# PMM.net
KiCad netlist of a schematic drawn in EAGLE
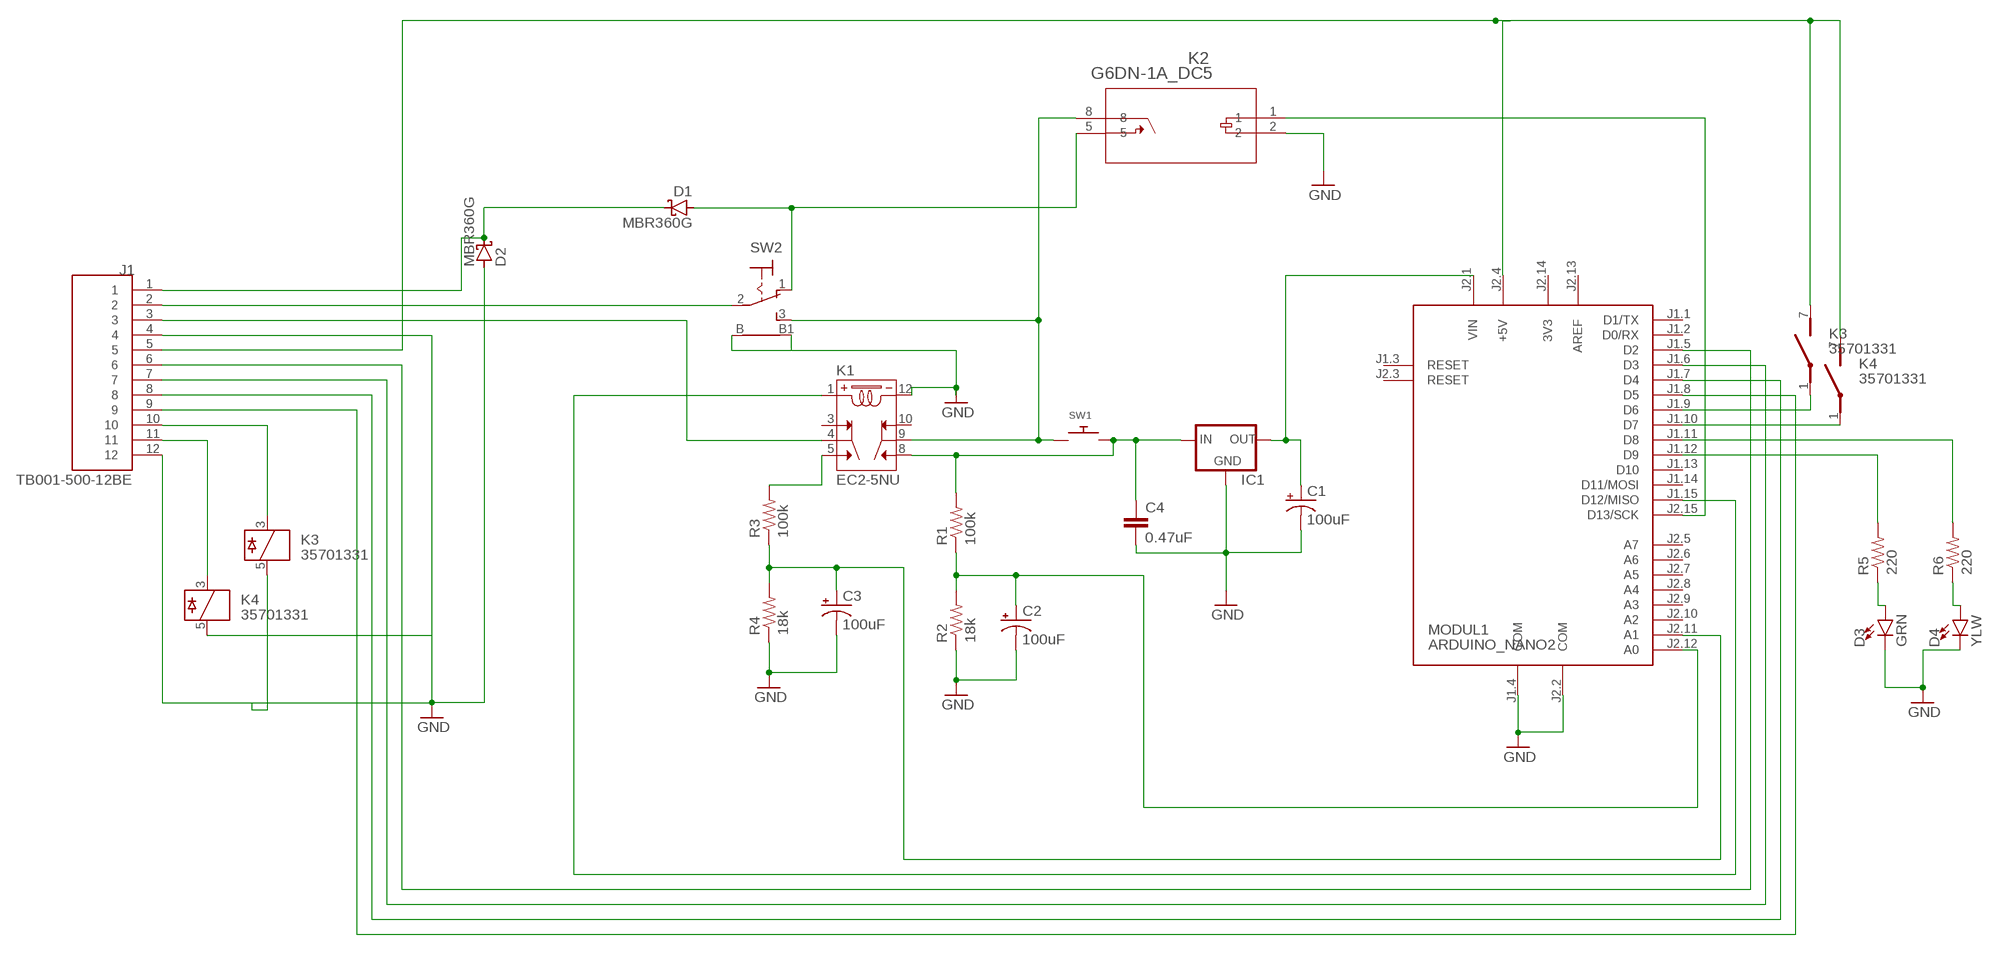
[diagram p0: schematic, sheet 1]

(export (version "E")
  (design (tool "Eeschema 10.0.6"))
  (components
    (comp (ref "C1")
      (value "100uF")
      (footprint "eagle-import:E2,5-7")
      (libsource (lib "eagle-import") (part "CPOL-USE2.5-7"))
    )
    (comp (ref "C2")
      (value "100uF")
      (footprint "eagle-import:E2,5-7")
      (libsource (lib "eagle-import") (part "CPOL-USE2.5-7"))
    )
    (comp (ref "C3")
      (value "100uF")
      (footprint "eagle-import:E2,5-7")
      (libsource (lib "eagle-import") (part "CPOL-USE2.5-7"))
    )
    (comp (ref "C4")
      (value "0.47uF")
      (footprint "eagle-import:C10B6")
      (libsource (lib "eagle-import") (part "C10/6"))
    )
    (comp (ref "D1")
      (value "MBR360G")
      (footprint "eagle-import:DO201AD")
      (fields
        (field (name "DIGIKEY_PART_NUMBER") "MBR360GOS-ND")
        (field (name "MANUFACTURER") "ON Semiconductor")
        (field (name "CREATED_BY") "PCBLayout.com")
      )
      (libsource (lib "eagle-import") (part "MBR360G"))
    )
    (comp (ref "D2")
      (value "MBR360G")
      (footprint "eagle-import:DO201AD")
      (fields
        (field (name "DIGIKEY_PART_NUMBER") "MBR360GOS-ND")
        (field (name "MANUFACTURER") "ON Semiconductor")
        (field (name "CREATED_BY") "PCBLayout.com")
      )
      (libsource (lib "eagle-import") (part "MBR360G"))
    )
    (comp (ref "D3")
      (value "GRN")
      (footprint "eagle-import:LED_5MM-KIT")
      (libsource (lib "eagle-import") (part "LED5MM-KIT"))
    )
    (comp (ref "D4")
      (value "YLW")
      (footprint "eagle-import:LED_5MM-KIT")
      (libsource (lib "eagle-import") (part "LED5MM-KIT"))
    )
    (comp (ref "IC1")
      (value "78XXS")
      (footprint "eagle-import:78XXS")
      (libsource (lib "eagle-import") (part "78XXS"))
    )
    (comp (ref "J1")
      (value "TB001-500-12BE")
      (footprint "eagle-import:CUI_TB001-500-12BE")
      (fields (field (name "MANUFACTURER") "CUI"))
      (libsource (lib "eagle-import") (part "TB001-500-12BE"))
    )
    (comp (ref "K1")
      (value "EC2-5NU")
      (footprint "eagle-import:RELAY_EC2-5NU")
      (fields (field (name "DIGI-KEY_PART_NUMBER") "399-11052-5-ND") (field (name "MF") "KEMET"))
      (libsource (lib "eagle-import") (part "EC2-5NU"))
    )
    (comp (ref "K2")
      (value "G6DN-1A_DC5")
      (footprint "eagle-import:RELAY_G6DN-1A_OMR")
      (fields
        (field (name "MANUFACTURER_PART_NUMBER") "G6DN-1A DC5")
        (field (name "COPYRIGHT") "Copyright (C) 2018 Accelerated Designs. All rights reserved")
      )
      (libsource (lib "eagle-import") (part "G6DN-1A_DC5"))
    )
    (comp (ref "K3")
      (value "35701331")
      (footprint "eagle-import:REED")
      (libsource (lib "eagle-import") (part "35701331"))
    )
    (comp (ref "K4")
      (value "35701331")
      (footprint "eagle-import:REED")
      (libsource (lib "eagle-import") (part "35701331"))
    )
    (comp (ref "MODUL1")
      (value "ARDUINO_NANO2")
      (footprint "eagle-import:ARDUINO_NANO2")
      (libsource (lib "eagle-import") (part "ARDUINO_NANO2"))
    )
    (comp (ref "R1")
      (value "100k")
      (footprint "eagle-import:0207_12")
      (libsource (lib "eagle-import") (part "R-US_0207/12"))
    )
    (comp (ref "R2")
      (value "18k")
      (footprint "eagle-import:0207_12")
      (libsource (lib "eagle-import") (part "R-US_0207/12"))
    )
    (comp (ref "R3")
      (value "100k")
      (footprint "eagle-import:0207_12")
      (libsource (lib "eagle-import") (part "R-US_0207/12"))
    )
    (comp (ref "R4")
      (value "18k")
      (footprint "eagle-import:0207_12")
      (libsource (lib "eagle-import") (part "R-US_0207/12"))
    )
    (comp (ref "R5")
      (value "220")
      (footprint "eagle-import:0207_12")
      (libsource (lib "eagle-import") (part "R-US_0207/12"))
    )
    (comp (ref "R6")
      (value "220")
      (footprint "eagle-import:0207_12")
      (libsource (lib "eagle-import") (part "R-US_0207/12"))
    )
    (comp (ref "SW1")
      (value "SWITCH_PUSHBUTTONON-MOM.2")
      (footprint "eagle-import:TACT_PANA-EVQ")
      (libsource (lib "eagle-import") (part "SWITCH_PUSHBUTTONON-MOM.2"))
    )
    (comp (ref "SW2")
      (value "M20130M2013S2A2W30")
      (footprint "eagle-import:M201_30")
      (libsource (lib "eagle-import") (part "M20130M2013S2A2W30"))
    )
  )
  (nets
    (net (code "1") (name "/3V3") (class "Default")
      (node (ref "MODUL1") (pin "J2.14") (pinfunction "3V3_J2.14") (pintype "power_in"))
    )
    (net (code "2") (name "/AREF") (class "Default")
      (node (ref "MODUL1") (pin "J2.13") (pinfunction "AREF_J2.13") (pintype "power_in"))
    )
    (net (code "3") (name "GND") (class "Default")
      (node (ref "C1") (pin "-") (pinfunction "-_-") (pintype "passive"))
      (node (ref "C2") (pin "-") (pinfunction "-_-") (pintype "passive"))
      (node (ref "C3") (pin "-") (pinfunction "-_-") (pintype "passive"))
      (node (ref "C4") (pin "2") (pinfunction "2_2") (pintype "passive"))
      (node (ref "D2") (pin "A") (pinfunction "A_A") (pintype "passive"))
      (node (ref "D3") (pin "K") (pinfunction "C_K") (pintype "passive"))
      (node (ref "D4") (pin "K") (pinfunction "C_K") (pintype "passive"))
      (node (ref "IC1") (pin "GND") (pinfunction "GND_GND") (pintype "input"))
      (node (ref "J1") (pin "12") (pinfunction "12_12") (pintype "passive"))
      (node (ref "J1") (pin "4") (pinfunction "4_4") (pintype "passive"))
      (node (ref "K1") (pin "12") (pinfunction "12_12") (pintype "passive"))
      (node (ref "K2") (pin "2") (pinfunction "2_2") (pintype "passive"))
      (node (ref "K3") (pin "5") (pinfunction "5_5") (pintype "passive"))
      (node (ref "K4") (pin "5") (pinfunction "5_5") (pintype "passive"))
      (node (ref "MODUL1") (pin "J1.4") (pinfunction "COM_J1.4") (pintype "power_in"))
      (node (ref "MODUL1") (pin "J2.2") (pinfunction "COM_J2.2") (pintype "power_in"))
      (node (ref "R2") (pin "1") (pinfunction "1_1") (pintype "passive"))
      (node (ref "R4") (pin "1") (pinfunction "1_1") (pintype "passive"))
      (node (ref "SW2") (pin "B") (pinfunction "B_B") (pintype "passive"))
      (node (ref "SW2") (pin "B1") (pinfunction "B1_B1") (pintype "passive"))
    )
    (net (code "4") (name "Net-(C4-Pad1)") (class "Default")
      (node (ref "C4") (pin "1") (pinfunction "1_1") (pintype "passive"))
      (node (ref "IC1") (pin "IN") (pinfunction "IN_IN") (pintype "input"))
      (node (ref "K1") (pin "8") (pinfunction "8_8") (pintype "passive"))
      (node (ref "R1") (pin "2") (pinfunction "2_2") (pintype "passive"))
      (node (ref "SW1") (pin "P$2") (pinfunction "P$2_P$2") (pintype "passive"))
    )
    (net (code "5") (name "Net-(D1-PadC)") (class "Default")
      (node (ref "D1") (pin "C") (pinfunction "C_C") (pintype "passive"))
      (node (ref "D2") (pin "C") (pinfunction "C_C") (pintype "passive"))
      (node (ref "J1") (pin "1") (pinfunction "1_1") (pintype "passive"))
    )
    (net (code "6") (name "Net-(D3-PadA)") (class "Default")
      (node (ref "D3") (pin "A") (pinfunction "A_A") (pintype "passive"))
      (node (ref "R5") (pin "1") (pinfunction "1_1") (pintype "passive"))
    )
    (net (code "7") (name "Net-(D4-PadA)") (class "Default")
      (node (ref "D4") (pin "A") (pinfunction "A_A") (pintype "passive"))
      (node (ref "R6") (pin "1") (pinfunction "1_1") (pintype "passive"))
    )
    (net (code "8") (name "Net-(J1-Pad3)") (class "Default")
      (node (ref "J1") (pin "3") (pinfunction "3_3") (pintype "passive"))
      (node (ref "K1") (pin "4") (pinfunction "4_4") (pintype "passive"))
    )
    (net (code "9") (name "Net-(J1-Pad10)") (class "Default")
      (node (ref "J1") (pin "10") (pinfunction "10_10") (pintype "passive"))
      (node (ref "K3") (pin "3") (pinfunction "3_3") (pintype "passive"))
    )
    (net (code "10") (name "Net-(J1-Pad11)") (class "Default")
      (node (ref "J1") (pin "11") (pinfunction "11_11") (pintype "passive"))
      (node (ref "K4") (pin "3") (pinfunction "3_3") (pintype "passive"))
    )
    (net (code "11") (name "Net-(K1-Pad5)") (class "Default")
      (node (ref "K1") (pin "5") (pinfunction "5_5") (pintype "passive"))
      (node (ref "R3") (pin "2") (pinfunction "2_2") (pintype "passive"))
    )
    (net (code "12") (name "Net-(K3B-P)") (class "Default")
      (node (ref "K3") (pin "1") (pinfunction "P_1") (pintype "passive"))
      (node (ref "MODUL1") (pin "J1.9") (pinfunction "D6_J1.9") (pintype "bidirectional"))
    )
    (net (code "13") (name "Net-(K3B-S)") (class "Default")
      (node (ref "J1") (pin "5") (pinfunction "5_5") (pintype "passive"))
      (node (ref "K3") (pin "7") (pinfunction "S_7") (pintype "passive"))
      (node (ref "K4") (pin "7") (pinfunction "S_7") (pintype "passive"))
      (node (ref "MODUL1") (pin "J2.4") (pinfunction "+5V_J2.4") (pintype "power_in"))
    )
    (net (code "14") (name "Net-(K4B-P)") (class "Default")
      (node (ref "K4") (pin "1") (pinfunction "P_1") (pintype "passive"))
      (node (ref "MODUL1") (pin "J1.10") (pinfunction "D7_J1.10") (pintype "bidirectional"))
    )
    (net (code "15") (name "Net-(MODUL1-A0)") (class "Default")
      (node (ref "C2") (pin "+") (pinfunction "+_+") (pintype "passive"))
      (node (ref "MODUL1") (pin "J2.12") (pinfunction "A0_J2.12") (pintype "bidirectional"))
      (node (ref "R1") (pin "1") (pinfunction "1_1") (pintype "passive"))
      (node (ref "R2") (pin "2") (pinfunction "2_2") (pintype "passive"))
    )
    (net (code "16") (name "Net-(MODUL1-A1)") (class "Default")
      (node (ref "C3") (pin "+") (pinfunction "+_+") (pintype "passive"))
      (node (ref "MODUL1") (pin "J2.11") (pinfunction "A1_J2.11") (pintype "bidirectional"))
      (node (ref "R3") (pin "1") (pinfunction "1_1") (pintype "passive"))
      (node (ref "R4") (pin "2") (pinfunction "2_2") (pintype "passive"))
    )
    (net (code "17") (name "Net-(MODUL1-D2)") (class "Default")
      (node (ref "J1") (pin "6") (pinfunction "6_6") (pintype "passive"))
      (node (ref "MODUL1") (pin "J1.5") (pinfunction "D2_J1.5") (pintype "bidirectional"))
    )
    (net (code "18") (name "Net-(MODUL1-D3)") (class "Default")
      (node (ref "J1") (pin "7") (pinfunction "7_7") (pintype "passive"))
      (node (ref "MODUL1") (pin "J1.6") (pinfunction "D3_J1.6") (pintype "bidirectional"))
    )
    (net (code "19") (name "Net-(MODUL1-D4)") (class "Default")
      (node (ref "J1") (pin "8") (pinfunction "8_8") (pintype "passive"))
      (node (ref "MODUL1") (pin "J1.7") (pinfunction "D4_J1.7") (pintype "bidirectional"))
    )
    (net (code "20") (name "Net-(MODUL1-D5)") (class "Default")
      (node (ref "J1") (pin "9") (pinfunction "9_9") (pintype "passive"))
      (node (ref "MODUL1") (pin "J1.8") (pinfunction "D5_J1.8") (pintype "bidirectional"))
    )
    (net (code "21") (name "Net-(MODUL1-D8)") (class "Default")
      (node (ref "MODUL1") (pin "J1.11") (pinfunction "D8_J1.11") (pintype "bidirectional"))
      (node (ref "R6") (pin "2") (pinfunction "2_2") (pintype "passive"))
    )
    (net (code "22") (name "Net-(MODUL1-D9)") (class "Default")
      (node (ref "MODUL1") (pin "J1.12") (pinfunction "D9_J1.12") (pintype "bidirectional"))
      (node (ref "R5") (pin "2") (pinfunction "2_2") (pintype "passive"))
    )
    (net (code "23") (name "Net-(MODUL1-D12{slash}MISO)") (class "Default")
      (node (ref "K1") (pin "1") (pinfunction "1_1") (pintype "passive"))
      (node (ref "MODUL1") (pin "J1.15") (pinfunction "D12/MISO_J1.15") (pintype "bidirectional"))
    )
    (net (code "24") (name "Net-(MODUL1-D13{slash}SCK)") (class "Default")
      (node (ref "K2") (pin "1") (pinfunction "1_1") (pintype "passive"))
      (node (ref "MODUL1") (pin "J2.15") (pinfunction "D13/SCK_J2.15") (pintype "bidirectional"))
    )
    (net (code "25") (name "Net-(MODUL1-VIN)") (class "Default")
      (node (ref "C1") (pin "+") (pinfunction "+_+") (pintype "passive"))
      (node (ref "IC1") (pin "OUT") (pinfunction "OUT_OUT") (pintype "passive"))
      (node (ref "MODUL1") (pin "J2.1") (pinfunction "VIN_J2.1") (pintype "power_in"))
    )
    (net (code "26") (name "Net-(SW2-O)") (class "Default")
      (node (ref "D1") (pin "A") (pinfunction "A_A") (pintype "passive"))
      (node (ref "K2") (pin "5") (pinfunction "5_5") (pintype "passive"))
      (node (ref "SW2") (pin "1") (pinfunction "O_1") (pintype "passive"))
    )
    (net (code "27") (name "Net-(SW2-P)") (class "Default")
      (node (ref "J1") (pin "2") (pinfunction "2_2") (pintype "passive"))
      (node (ref "SW2") (pin "2") (pinfunction "P_2") (pintype "passive"))
    )
    (net (code "28") (name "Net-(SW2-S)") (class "Default")
      (node (ref "K1") (pin "9") (pinfunction "9_9") (pintype "passive"))
      (node (ref "K2") (pin "8") (pinfunction "8_8") (pintype "passive"))
      (node (ref "SW1") (pin "P$1") (pinfunction "P$1_P$1") (pintype "passive"))
      (node (ref "SW2") (pin "3") (pinfunction "S_3") (pintype "passive"))
    )
    (net (code "29") (name "unconnected-(K1-Pad3)") (class "Default")
      (node (ref "K1") (pin "3") (pinfunction "3_3") (pintype "passive"))
    )
    (net (code "30") (name "unconnected-(K1-Pad10)") (class "Default")
      (node (ref "K1") (pin "10") (pinfunction "10_10") (pintype "passive"))
    )
    (net (code "31") (name "unconnected-(MODUL1-A2-PadJ2.10)") (class "Default")
      (node (ref "MODUL1") (pin "J2.10") (pinfunction "A2_J2.10") (pintype "bidirectional"))
    )
    (net (code "32") (name "unconnected-(MODUL1-A3-PadJ2.9)") (class "Default")
      (node (ref "MODUL1") (pin "J2.9") (pinfunction "A3_J2.9") (pintype "bidirectional"))
    )
    (net (code "33") (name "unconnected-(MODUL1-A4-PadJ2.8)") (class "Default")
      (node (ref "MODUL1") (pin "J2.8") (pinfunction "A4_J2.8") (pintype "bidirectional"))
    )
    (net (code "34") (name "unconnected-(MODUL1-A5-PadJ2.7)") (class "Default")
      (node (ref "MODUL1") (pin "J2.7") (pinfunction "A5_J2.7") (pintype "bidirectional"))
    )
    (net (code "35") (name "unconnected-(MODUL1-A6-PadJ2.6)") (class "Default")
      (node (ref "MODUL1") (pin "J2.6") (pinfunction "A6_J2.6") (pintype "bidirectional"))
    )
    (net (code "36") (name "unconnected-(MODUL1-A7-PadJ2.5)") (class "Default")
      (node (ref "MODUL1") (pin "J2.5") (pinfunction "A7_J2.5") (pintype "bidirectional"))
    )
    (net (code "37") (name "unconnected-(MODUL1-D0{slash}RX-PadJ1.2)") (class "Default")
      (node (ref "MODUL1") (pin "J1.2") (pinfunction "D0/RX_J1.2") (pintype "bidirectional"))
    )
    (net (code "38") (name "unconnected-(MODUL1-D1{slash}TX-PadJ1.1)") (class "Default")
      (node (ref "MODUL1") (pin "J1.1") (pinfunction "D1/TX_J1.1") (pintype "bidirectional"))
    )
    (net (code "39") (name "unconnected-(MODUL1-D10-PadJ1.13)") (class "Default")
      (node (ref "MODUL1") (pin "J1.13") (pinfunction "D10_J1.13") (pintype "bidirectional"))
    )
    (net (code "40") (name "unconnected-(MODUL1-D11{slash}MOSI-PadJ1.14)") (class "Default")
      (node (ref "MODUL1") (pin "J1.14") (pinfunction "D11/MOSI_J1.14") (pintype "bidirectional"))
    )
    (net (code "41") (name "unconnected-(MODUL1-RESET-PadJ1.3)") (class "Default")
      (node (ref "MODUL1") (pin "J1.3") (pinfunction "RESET_J1.3") (pintype "bidirectional"))
    )
    (net (code "42") (name "unconnected-(MODUL1-RESET-PadJ2.3)") (class "Default")
      (node (ref "MODUL1") (pin "J2.3") (pinfunction "RESET_J2.3") (pintype "bidirectional"))
    )
  )
)
